# main.net
KiCad netlist of a schematic drawn in Altium Designer
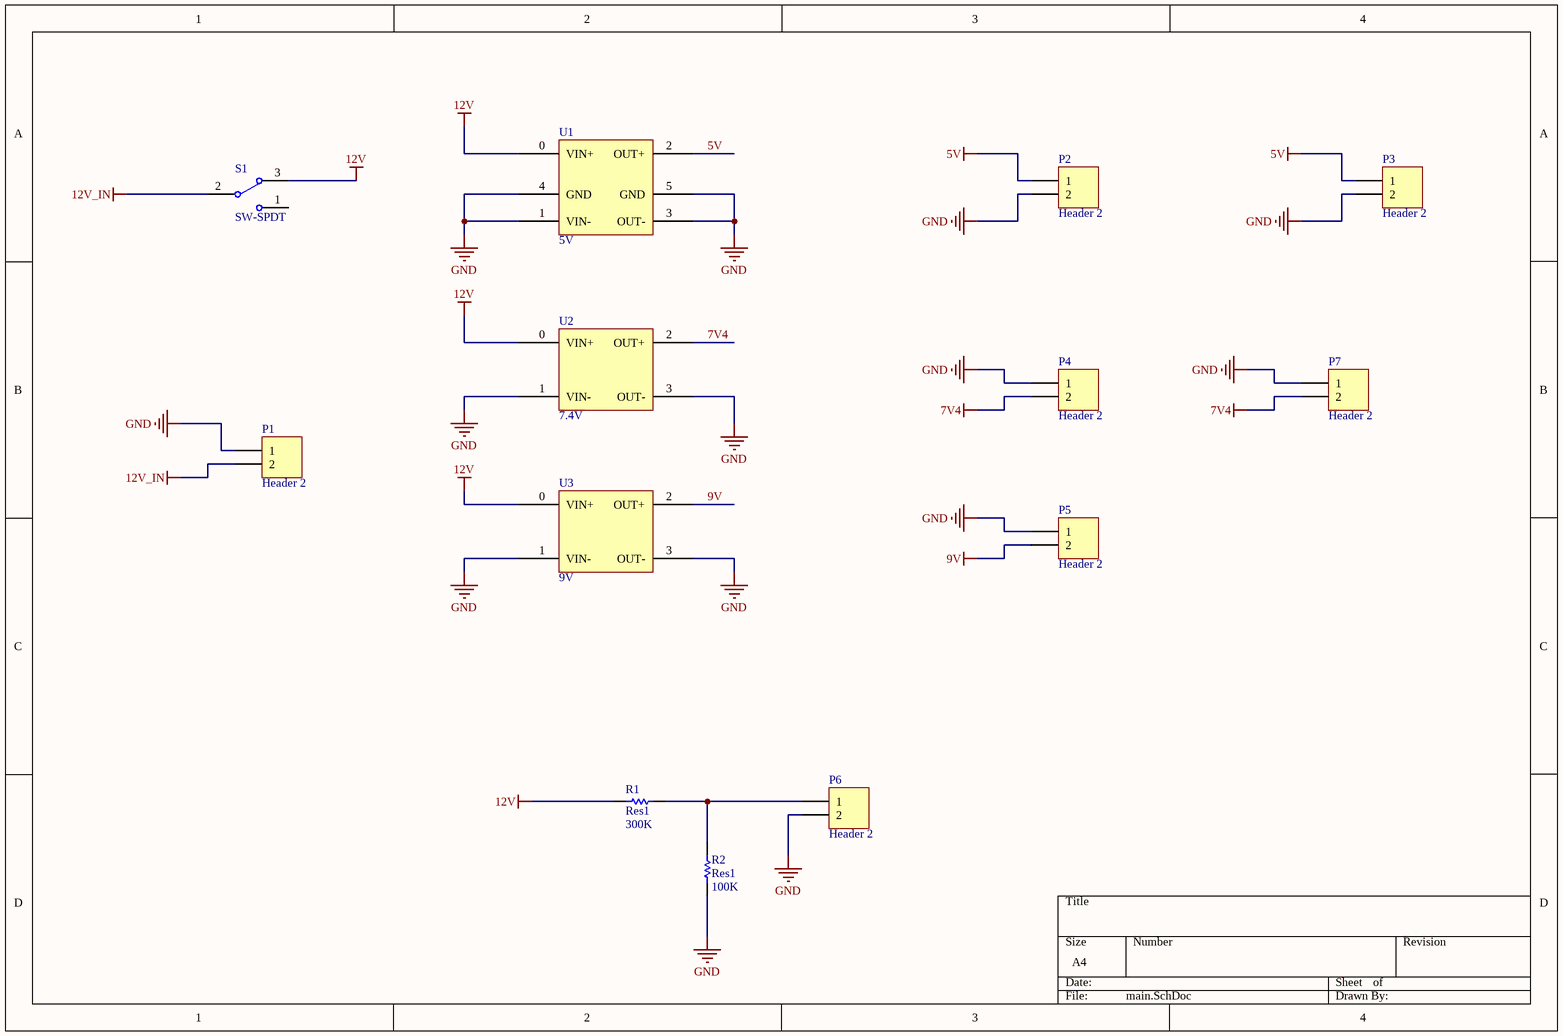
[diagram p0: main.SchDoc]

(export (version "E")
  (design (tool "Eeschema 10.0.6"))
  (components
    (comp (ref "P1")
      (value "Header 2")
      (footprint "CONN-TH_XT30UPB-M")
      (description "Header, 2-Pin")
      (fields (field (name "PUBLISHER") "Altium Limited"))
      (libsource (lib "Miscellaneous Connectors") (part "Header 2"))
    )
    (comp (ref "P2")
      (value "Header 2")
      (footprint "XH2.54-2A")
      (description "Header, 2-Pin")
      (fields (field (name "PUBLISHER") "Altium Limited"))
      (libsource (lib "Miscellaneous Connectors") (part "Header 2"))
    )
    (comp (ref "P3")
      (value "Header 2")
      (footprint "XH2.54-2A")
      (description "Header, 2-Pin")
      (fields (field (name "PUBLISHER") "Altium Limited"))
      (libsource (lib "Miscellaneous Connectors") (part "Header 2"))
    )
    (comp (ref "P4")
      (value "Header 2")
      (footprint "XH2.54-2A")
      (description "Header, 2-Pin")
      (fields (field (name "PUBLISHER") "Altium Limited"))
      (libsource (lib "Miscellaneous Connectors") (part "Header 2"))
    )
    (comp (ref "P5")
      (value "Header 2")
      (footprint "XH2.54-2A")
      (description "Header, 2-Pin")
      (fields (field (name "PUBLISHER") "Altium Limited"))
      (libsource (lib "Miscellaneous Connectors") (part "Header 2"))
    )
    (comp (ref "P6")
      (value "Header 2")
      (footprint "XH2.54-2A")
      (description "Header, 2-Pin")
      (fields (field (name "PUBLISHER") "Altium Limited"))
      (libsource (lib "Miscellaneous Connectors") (part "Header 2"))
    )
    (comp (ref "P7")
      (value "Header 2")
      (footprint "XH2.54-2A")
      (description "Header, 2-Pin")
      (fields (field (name "PUBLISHER") "Altium Limited"))
      (libsource (lib "Miscellaneous Connectors") (part "Header 2"))
    )
    (comp (ref "R1")
      (value "Res1")
      (footprint "R0603")
      (description "Resistor")
      (fields (field (name "ALTIUM_VALUE") "300K") (field (name "PUBLISHER") "Altium Limited"))
      (libsource (lib "Miscellaneous Devices") (part "Res1"))
    )
    (comp (ref "R2")
      (value "Res1")
      (footprint "R0603")
      (description "Resistor")
      (fields (field (name "ALTIUM_VALUE") "100K") (field (name "PUBLISHER") "Altium Limited"))
      (libsource (lib "Miscellaneous Devices") (part "Res1"))
    )
    (comp (ref "S1")
      (value "SW-SPDT")
      (footprint "switch")
      (description "SPDT Subminiature Toggle Switch, Right Angle Mounting, Vertical Actuation")
      (fields (field (name "PUBLISHER") "Altium Limited"))
      (libsource (lib "Miscellaneous Devices") (part "SW-SPDT"))
    )
    (comp (ref "U1") (value "5V") (footprint "5V_8A") (libsource (lib "5V_8A") (part "5V_8A")))
    (comp (ref "U2") (value "7.4V") (footprint "PCBComponent_1") (libsource (lib "7_4V") (part "7_4V")))
    (comp (ref "U3") (value "9V") (footprint "PCBComponent_1") (libsource (lib "9V") (part "9V")))
  )
  (nets
    (net (code "1") (name "5V") (class "Default")
      (node (ref "P2") (pin "1") (pinfunction "1_1") (pintype "passive"))
      (node (ref "P3") (pin "1") (pinfunction "1_1") (pintype "passive"))
      (node (ref "U1") (pin "2") (pinfunction "OUT+_2") (pintype "passive"))
    )
    (net (code "2") (name "7V4") (class "Default")
      (node (ref "P4") (pin "2") (pinfunction "2_2") (pintype "passive"))
      (node (ref "P7") (pin "2") (pinfunction "2_2") (pintype "passive"))
      (node (ref "U2") (pin "2") (pinfunction "OUT+_2") (pintype "passive"))
    )
    (net (code "3") (name "9V") (class "Default")
      (node (ref "P5") (pin "2") (pinfunction "2_2") (pintype "passive"))
      (node (ref "U3") (pin "2") (pinfunction "OUT+_2") (pintype "passive"))
    )
    (net (code "4") (name "12V") (class "Default")
      (node (ref "R1") (pin "2") (pinfunction "2_2") (pintype "passive"))
      (node (ref "S1") (pin "3") (pinfunction "3_3") (pintype "passive"))
      (node (ref "U1") (pin "0") (pinfunction "VIN+_0") (pintype "passive"))
      (node (ref "U2") (pin "0") (pinfunction "VIN+_0") (pintype "passive"))
      (node (ref "U3") (pin "0") (pinfunction "VIN+_0") (pintype "passive"))
    )
    (net (code "5") (name "12V_IN") (class "Default")
      (node (ref "P1") (pin "2") (pinfunction "2_2") (pintype "passive"))
      (node (ref "S1") (pin "2") (pinfunction "2_2") (pintype "passive"))
    )
    (net (code "6") (name "GND") (class "Default")
      (node (ref "P1") (pin "1") (pinfunction "1_1") (pintype "passive"))
      (node (ref "P2") (pin "2") (pinfunction "2_2") (pintype "passive"))
      (node (ref "P3") (pin "2") (pinfunction "2_2") (pintype "passive"))
      (node (ref "P4") (pin "1") (pinfunction "1_1") (pintype "passive"))
      (node (ref "P5") (pin "1") (pinfunction "1_1") (pintype "passive"))
      (node (ref "P6") (pin "2") (pinfunction "2_2") (pintype "passive"))
      (node (ref "P7") (pin "1") (pinfunction "1_1") (pintype "passive"))
      (node (ref "R2") (pin "1") (pinfunction "1_1") (pintype "passive"))
      (node (ref "U1") (pin "1") (pinfunction "VIN-_1") (pintype "passive"))
      (node (ref "U1") (pin "3") (pinfunction "OUT-_3") (pintype "passive"))
      (node (ref "U1") (pin "4") (pinfunction "GND_4") (pintype "passive"))
      (node (ref "U1") (pin "5") (pinfunction "GND_5") (pintype "passive"))
      (node (ref "U2") (pin "1") (pinfunction "VIN-_1") (pintype "passive"))
      (node (ref "U2") (pin "3") (pinfunction "OUT-_3") (pintype "passive"))
      (node (ref "U3") (pin "1") (pinfunction "VIN-_1") (pintype "passive"))
      (node (ref "U3") (pin "3") (pinfunction "OUT-_3") (pintype "passive"))
    )
    (net (code "7") (name "Net-(P6-Pad1)") (class "Default")
      (node (ref "P6") (pin "1") (pinfunction "1_1") (pintype "passive"))
      (node (ref "R1") (pin "1") (pinfunction "1_1") (pintype "passive"))
      (node (ref "R2") (pin "2") (pinfunction "2_2") (pintype "passive"))
    )
    (net (code "8") (name "unconnected-(S1-Pad1)") (class "Default")
      (node (ref "S1") (pin "1") (pinfunction "1_1") (pintype "passive"))
    )
  )
)
